# 4_waffling60-DB_periferals.net
KiCad netlist of a schematic drawn in Altium Designer
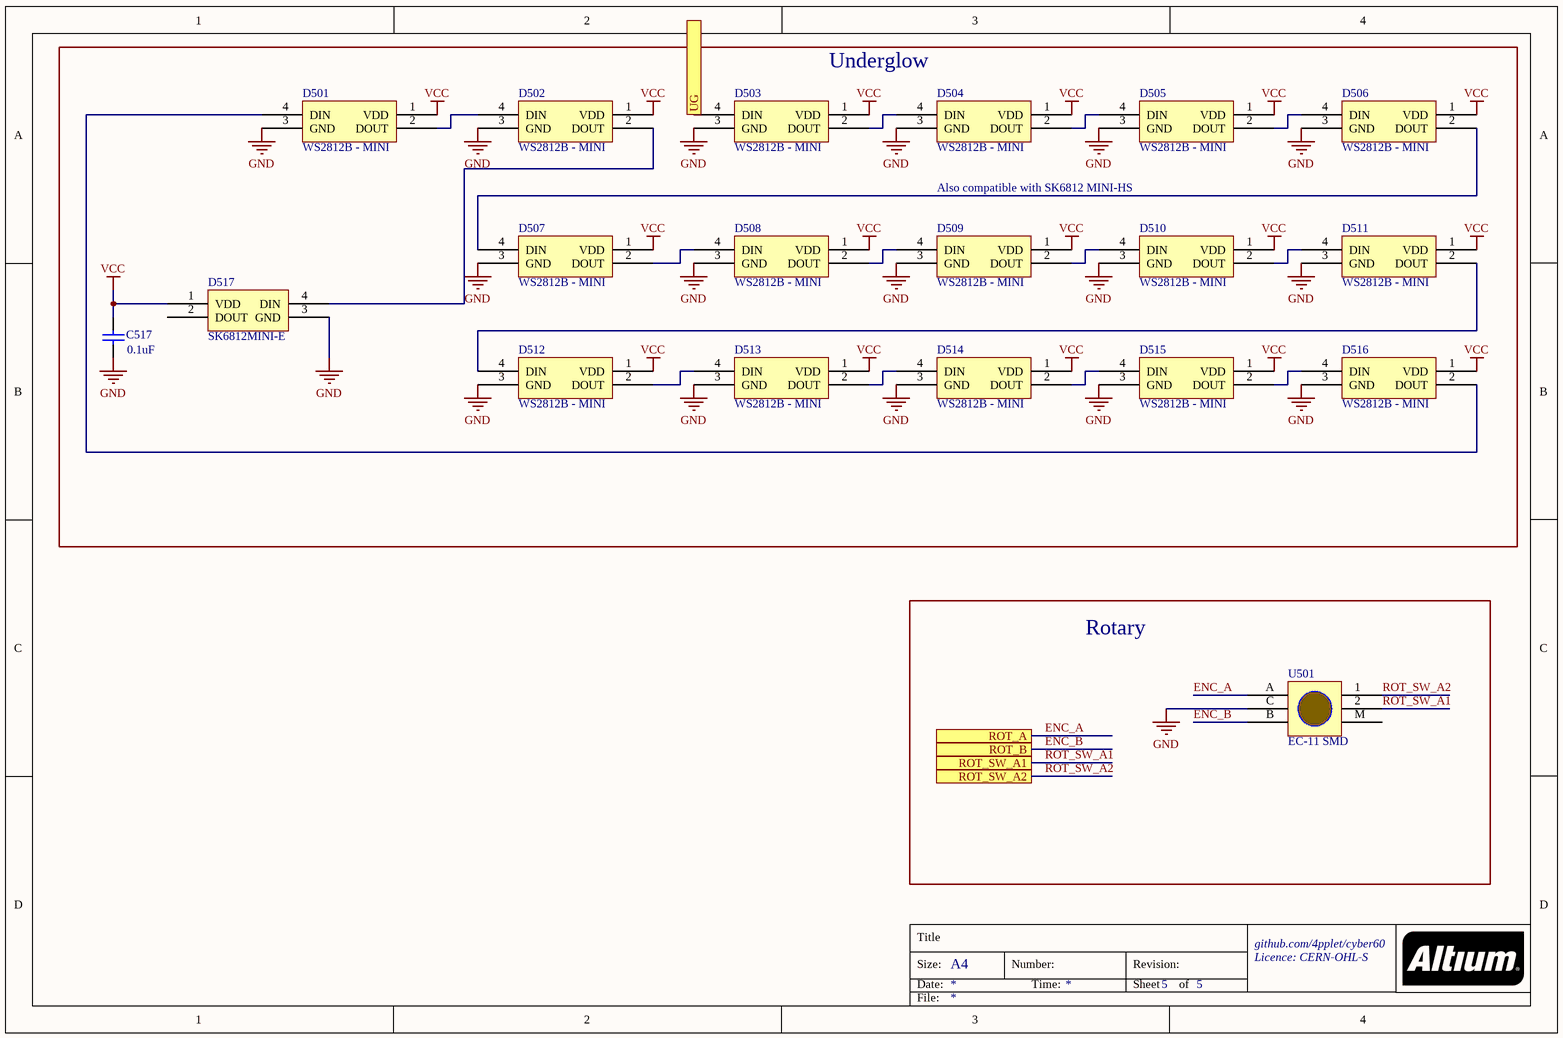
[diagram p0: 4_waffling60-DB_periferals.SchDoc]

(export (version "E")
  (design (tool "Eeschema 10.0.6"))
  (components
    (comp (ref "C517")
      (value "0.1uF")
      (footprint "C0603[1608]")
      (description "Capacitor")
      (fields (field (name "LCSC PART #") "C14663") (field (name "MRF.PART") "CC0603KRX7R9BB104"))
      (libsource (lib "Miscellaneous Devices") (part "Cap"))
    )
    (comp (ref "D501")
      (value "WS2812B - MINI")
      (footprint "WS2812B - 2020")
      (fields (field (name "LCSC PART #") "C965555") (field (name "MRF.PART") "WS2812B-2020"))
      (libsource (lib "Keebs") (part "WS2812B"))
    )
    (comp (ref "D502")
      (value "WS2812B - MINI")
      (footprint "WS2812B - 2020")
      (fields (field (name "LCSC PART #") "C965555") (field (name "MRF.PART") "WS2812B-2020"))
      (libsource (lib "Keebs") (part "WS2812B"))
    )
    (comp (ref "D503")
      (value "WS2812B - MINI")
      (footprint "WS2812B - 2020")
      (fields (field (name "LCSC PART #") "C965555") (field (name "MRF.PART") "WS2812B-2020"))
      (libsource (lib "Keebs") (part "WS2812B"))
    )
    (comp (ref "D504")
      (value "WS2812B - MINI")
      (footprint "WS2812B - 2020")
      (fields (field (name "LCSC PART #") "C965555") (field (name "MRF.PART") "WS2812B-2020"))
      (libsource (lib "Keebs") (part "WS2812B"))
    )
    (comp (ref "D505")
      (value "WS2812B - MINI")
      (footprint "WS2812B - 2020")
      (fields (field (name "LCSC PART #") "C965555") (field (name "MRF.PART") "WS2812B-2020"))
      (libsource (lib "Keebs") (part "WS2812B"))
    )
    (comp (ref "D506")
      (value "WS2812B - MINI")
      (footprint "WS2812B - 2020")
      (fields (field (name "LCSC PART #") "C965555") (field (name "MRF.PART") "WS2812B-2020"))
      (libsource (lib "Keebs") (part "WS2812B"))
    )
    (comp (ref "D507")
      (value "WS2812B - MINI")
      (footprint "WS2812B - 2020")
      (fields (field (name "LCSC PART #") "C965555") (field (name "MRF.PART") "WS2812B-2020"))
      (libsource (lib "Keebs") (part "WS2812B"))
    )
    (comp (ref "D508")
      (value "WS2812B - MINI")
      (footprint "WS2812B - 2020")
      (fields (field (name "LCSC PART #") "C965555") (field (name "MRF.PART") "WS2812B-2020"))
      (libsource (lib "Keebs") (part "WS2812B"))
    )
    (comp (ref "D509")
      (value "WS2812B - MINI")
      (footprint "WS2812B - 2020")
      (fields (field (name "LCSC PART #") "C965555") (field (name "MRF.PART") "WS2812B-2020"))
      (libsource (lib "Keebs") (part "WS2812B"))
    )
    (comp (ref "D510")
      (value "WS2812B - MINI")
      (footprint "WS2812B - 2020")
      (fields (field (name "LCSC PART #") "C965555") (field (name "MRF.PART") "WS2812B-2020"))
      (libsource (lib "Keebs") (part "WS2812B"))
    )
    (comp (ref "D511")
      (value "WS2812B - MINI")
      (footprint "WS2812B - 2020")
      (fields (field (name "LCSC PART #") "C965555") (field (name "MRF.PART") "WS2812B-2020"))
      (libsource (lib "Keebs") (part "WS2812B"))
    )
    (comp (ref "D512")
      (value "WS2812B - MINI")
      (footprint "WS2812B - 2020")
      (fields (field (name "LCSC PART #") "C965555") (field (name "MRF.PART") "WS2812B-2020"))
      (libsource (lib "Keebs") (part "WS2812B"))
    )
    (comp (ref "D513")
      (value "WS2812B - MINI")
      (footprint "WS2812B - 2020")
      (fields (field (name "LCSC PART #") "C965555") (field (name "MRF.PART") "WS2812B-2020"))
      (libsource (lib "Keebs") (part "WS2812B"))
    )
    (comp (ref "D514")
      (value "WS2812B - MINI")
      (footprint "WS2812B - 2020")
      (fields (field (name "LCSC PART #") "C965555") (field (name "MRF.PART") "WS2812B-2020"))
      (libsource (lib "Keebs") (part "WS2812B"))
    )
    (comp (ref "D515")
      (value "WS2812B - MINI")
      (footprint "WS2812B - 2020")
      (fields (field (name "LCSC PART #") "C965555") (field (name "MRF.PART") "WS2812B-2020"))
      (libsource (lib "Keebs") (part "WS2812B"))
    )
    (comp (ref "D516")
      (value "WS2812B - MINI")
      (footprint "WS2812B - 2020")
      (fields (field (name "LCSC PART #") "C965555") (field (name "MRF.PART") "WS2812B-2020"))
      (libsource (lib "Keebs") (part "WS2812B"))
    )
    (comp (ref "D517")
      (value "SK6812MINI-E")
      (footprint "SK6812MINI-E - shaped")
      (fields (field (name "LCSC PART #") "C524051") (field (name "MRF.PART") "DY-S352818/RGBC/6812-2T"))
      (libsource (lib "Keebs") (part "SK6812MINI-E"))
    )
    (comp (ref "U501") (value "EC-11 SMD") (footprint "EC11-SMD") (libsource (lib "Keebs") (part "EC-11")))
  )
  (nets
    (net (code "1") (name "/ENC_A") (class "Default")
      (node (ref "U501") (pin "A") (pinfunction "B_A") (pintype "passive"))
    )
    (net (code "2") (name "/ENC_B") (class "Default")
      (node (ref "U501") (pin "B") (pinfunction "B_B") (pintype "passive"))
    )
    (net (code "3") (name "/ROT_SW_A1") (class "Default")
      (node (ref "U501") (pin "2") (pinfunction "2_2") (pintype "passive"))
    )
    (net (code "4") (name "/ROT_SW_A2") (class "Default")
      (node (ref "U501") (pin "1") (pinfunction "1_1") (pintype "passive"))
    )
    (net (code "5") (name "/UG") (class "Default")
      (node (ref "D503") (pin "4") (pinfunction "DIN_4") (pintype "passive"))
    )
    (net (code "6") (name "GND") (class "Default")
      (node (ref "C517") (pin "1") (pinfunction "1_1") (pintype "passive"))
      (node (ref "D501") (pin "3") (pinfunction "GND_3") (pintype "passive"))
      (node (ref "D502") (pin "3") (pinfunction "GND_3") (pintype "passive"))
      (node (ref "D503") (pin "3") (pinfunction "GND_3") (pintype "passive"))
      (node (ref "D504") (pin "3") (pinfunction "GND_3") (pintype "passive"))
      (node (ref "D505") (pin "3") (pinfunction "GND_3") (pintype "passive"))
      (node (ref "D506") (pin "3") (pinfunction "GND_3") (pintype "passive"))
      (node (ref "D507") (pin "3") (pinfunction "GND_3") (pintype "passive"))
      (node (ref "D508") (pin "3") (pinfunction "GND_3") (pintype "passive"))
      (node (ref "D509") (pin "3") (pinfunction "GND_3") (pintype "passive"))
      (node (ref "D510") (pin "3") (pinfunction "GND_3") (pintype "passive"))
      (node (ref "D511") (pin "3") (pinfunction "GND_3") (pintype "passive"))
      (node (ref "D512") (pin "3") (pinfunction "GND_3") (pintype "passive"))
      (node (ref "D513") (pin "3") (pinfunction "GND_3") (pintype "passive"))
      (node (ref "D514") (pin "3") (pinfunction "GND_3") (pintype "passive"))
      (node (ref "D515") (pin "3") (pinfunction "GND_3") (pintype "passive"))
      (node (ref "D516") (pin "3") (pinfunction "GND_3") (pintype "passive"))
      (node (ref "D517") (pin "3") (pinfunction "GND_3") (pintype "passive"))
      (node (ref "U501") (pin "C") (pinfunction "C_C") (pintype "passive"))
    )
    (net (code "7") (name "Net-(D501-DIN)") (class "Default")
      (node (ref "D501") (pin "4") (pinfunction "DIN_4") (pintype "passive"))
      (node (ref "D516") (pin "2") (pinfunction "DOUT_2") (pintype "passive"))
    )
    (net (code "8") (name "Net-(D501-DOUT)") (class "Default")
      (node (ref "D501") (pin "2") (pinfunction "DOUT_2") (pintype "passive"))
      (node (ref "D502") (pin "4") (pinfunction "DIN_4") (pintype "passive"))
    )
    (net (code "9") (name "Net-(D502-DOUT)") (class "Default")
      (node (ref "D502") (pin "2") (pinfunction "DOUT_2") (pintype "passive"))
      (node (ref "D517") (pin "4") (pinfunction "DIN_4") (pintype "passive"))
    )
    (net (code "10") (name "Net-(D503-DOUT)") (class "Default")
      (node (ref "D503") (pin "2") (pinfunction "DOUT_2") (pintype "passive"))
      (node (ref "D504") (pin "4") (pinfunction "DIN_4") (pintype "passive"))
    )
    (net (code "11") (name "Net-(D504-DOUT)") (class "Default")
      (node (ref "D504") (pin "2") (pinfunction "DOUT_2") (pintype "passive"))
      (node (ref "D505") (pin "4") (pinfunction "DIN_4") (pintype "passive"))
    )
    (net (code "12") (name "Net-(D505-DOUT)") (class "Default")
      (node (ref "D505") (pin "2") (pinfunction "DOUT_2") (pintype "passive"))
      (node (ref "D506") (pin "4") (pinfunction "DIN_4") (pintype "passive"))
    )
    (net (code "13") (name "Net-(D506-DOUT)") (class "Default")
      (node (ref "D506") (pin "2") (pinfunction "DOUT_2") (pintype "passive"))
      (node (ref "D507") (pin "4") (pinfunction "DIN_4") (pintype "passive"))
    )
    (net (code "14") (name "Net-(D507-DOUT)") (class "Default")
      (node (ref "D507") (pin "2") (pinfunction "DOUT_2") (pintype "passive"))
      (node (ref "D508") (pin "4") (pinfunction "DIN_4") (pintype "passive"))
    )
    (net (code "15") (name "Net-(D508-DOUT)") (class "Default")
      (node (ref "D508") (pin "2") (pinfunction "DOUT_2") (pintype "passive"))
      (node (ref "D509") (pin "4") (pinfunction "DIN_4") (pintype "passive"))
    )
    (net (code "16") (name "Net-(D509-DOUT)") (class "Default")
      (node (ref "D509") (pin "2") (pinfunction "DOUT_2") (pintype "passive"))
      (node (ref "D510") (pin "4") (pinfunction "DIN_4") (pintype "passive"))
    )
    (net (code "17") (name "Net-(D510-DOUT)") (class "Default")
      (node (ref "D510") (pin "2") (pinfunction "DOUT_2") (pintype "passive"))
      (node (ref "D511") (pin "4") (pinfunction "DIN_4") (pintype "passive"))
    )
    (net (code "18") (name "Net-(D511-DOUT)") (class "Default")
      (node (ref "D511") (pin "2") (pinfunction "DOUT_2") (pintype "passive"))
      (node (ref "D512") (pin "4") (pinfunction "DIN_4") (pintype "passive"))
    )
    (net (code "19") (name "Net-(D512-DOUT)") (class "Default")
      (node (ref "D512") (pin "2") (pinfunction "DOUT_2") (pintype "passive"))
      (node (ref "D513") (pin "4") (pinfunction "DIN_4") (pintype "passive"))
    )
    (net (code "20") (name "Net-(D513-DOUT)") (class "Default")
      (node (ref "D513") (pin "2") (pinfunction "DOUT_2") (pintype "passive"))
      (node (ref "D514") (pin "4") (pinfunction "DIN_4") (pintype "passive"))
    )
    (net (code "21") (name "Net-(D514-DOUT)") (class "Default")
      (node (ref "D514") (pin "2") (pinfunction "DOUT_2") (pintype "passive"))
      (node (ref "D515") (pin "4") (pinfunction "DIN_4") (pintype "passive"))
    )
    (net (code "22") (name "Net-(D515-DOUT)") (class "Default")
      (node (ref "D515") (pin "2") (pinfunction "DOUT_2") (pintype "passive"))
      (node (ref "D516") (pin "4") (pinfunction "DIN_4") (pintype "passive"))
    )
    (net (code "23") (name "VCC") (class "Default")
      (node (ref "C517") (pin "2") (pinfunction "2_2") (pintype "passive"))
      (node (ref "D501") (pin "1") (pinfunction "VDD_1") (pintype "passive"))
      (node (ref "D502") (pin "1") (pinfunction "VDD_1") (pintype "passive"))
      (node (ref "D503") (pin "1") (pinfunction "VDD_1") (pintype "passive"))
      (node (ref "D504") (pin "1") (pinfunction "VDD_1") (pintype "passive"))
      (node (ref "D505") (pin "1") (pinfunction "VDD_1") (pintype "passive"))
      (node (ref "D506") (pin "1") (pinfunction "VDD_1") (pintype "passive"))
      (node (ref "D507") (pin "1") (pinfunction "VDD_1") (pintype "passive"))
      (node (ref "D508") (pin "1") (pinfunction "VDD_1") (pintype "passive"))
      (node (ref "D509") (pin "1") (pinfunction "VDD_1") (pintype "passive"))
      (node (ref "D510") (pin "1") (pinfunction "VDD_1") (pintype "passive"))
      (node (ref "D511") (pin "1") (pinfunction "VDD_1") (pintype "passive"))
      (node (ref "D512") (pin "1") (pinfunction "VDD_1") (pintype "passive"))
      (node (ref "D513") (pin "1") (pinfunction "VDD_1") (pintype "passive"))
      (node (ref "D514") (pin "1") (pinfunction "VDD_1") (pintype "passive"))
      (node (ref "D515") (pin "1") (pinfunction "VDD_1") (pintype "passive"))
      (node (ref "D516") (pin "1") (pinfunction "VDD_1") (pintype "passive"))
      (node (ref "D517") (pin "1") (pinfunction "VDD_1") (pintype "passive"))
    )
    (net (code "24") (name "unconnected-(D517-DOUT-Pad2)") (class "Default")
      (node (ref "D517") (pin "2") (pinfunction "DOUT_2") (pintype "passive"))
    )
    (net (code "25") (name "unconnected-(U501-PadM)") (class "Default")
      (node (ref "U501") (pin "M") (pinfunction "M_M") (pintype "passive"))
    )
  )
)
